# 6-CODEC.net
KiCad netlist of a schematic drawn in Altium Designer
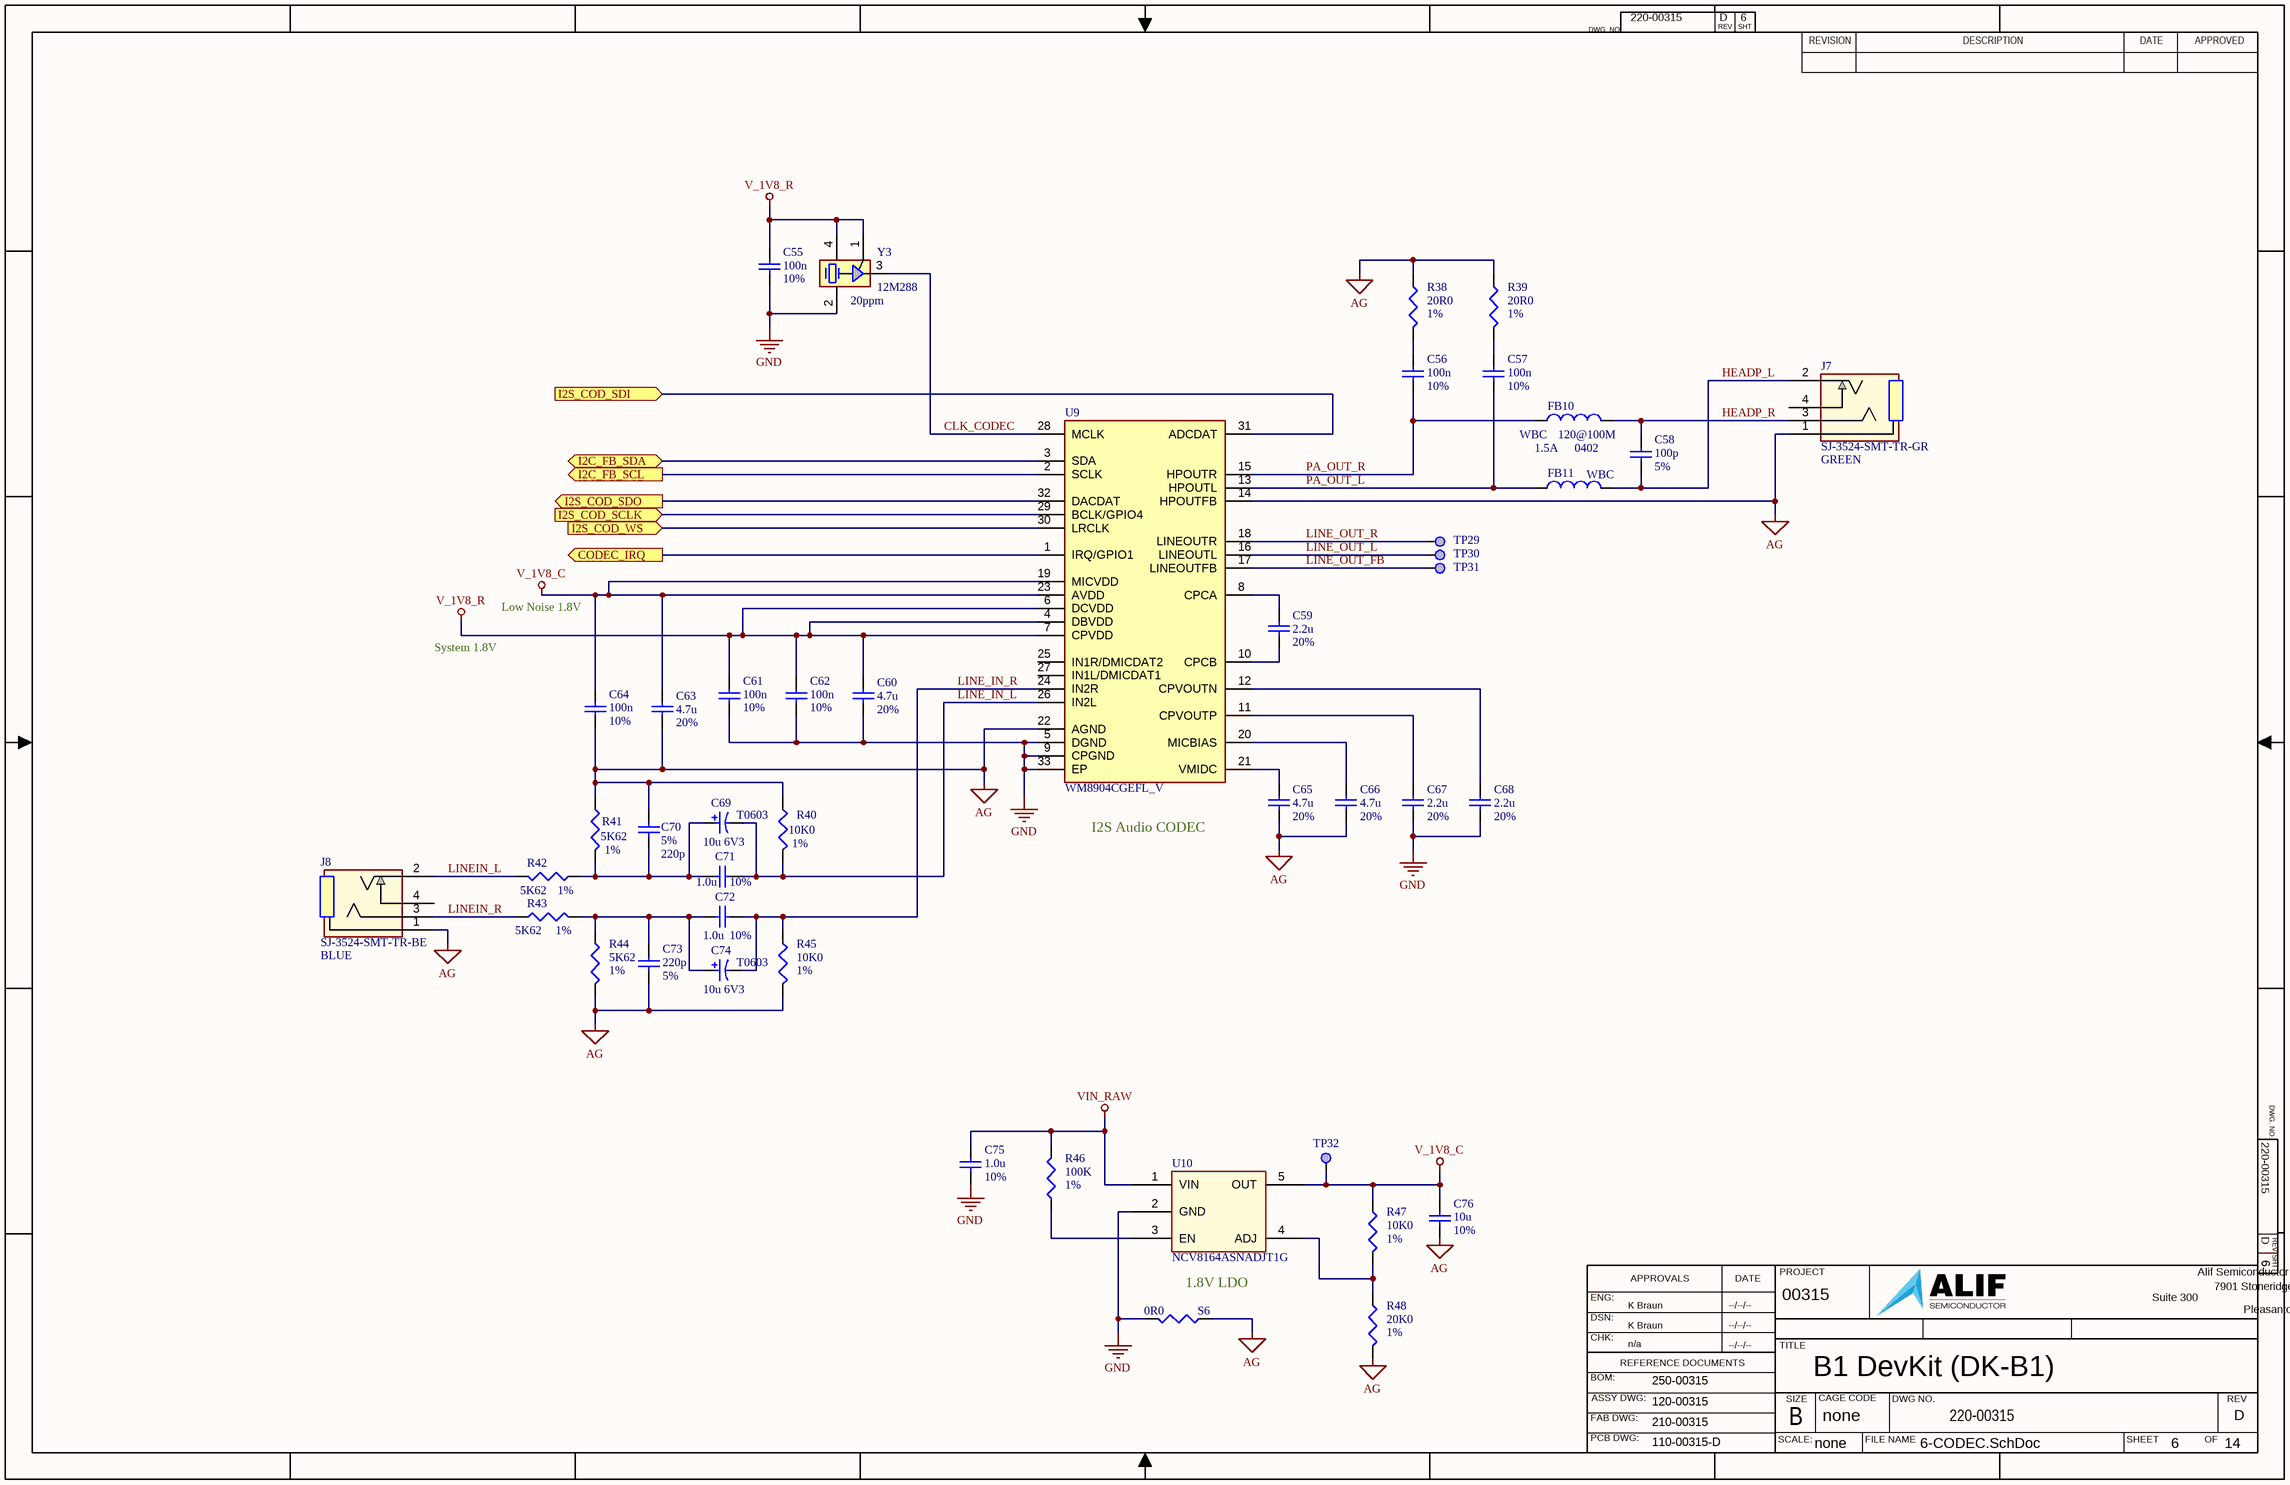
[diagram p0: 6-CODEC.SchDoc]

(export (version "E")
  (design (tool "Eeschema 10.0.6"))
  (components
    (comp (ref "C55")
      (value "100n")
      (footprint "CAPC0402-01")
      (description "Cap,100nF,10%,50V,X7R,0402")
      (fields
        (field (name "VOLTAGE") "50V")
        (field (name "TOLERANCE") "10%")
        (field (name "Comment") "Cap")
        (field (name "PUBLISHER") "Altium Limited")
      )
      (libsource (lib "kb1") (part "Cap"))
    )
    (comp (ref "C56")
      (value "100n")
      (footprint "CAPC0402-01")
      (description "Cap,100nF,10%,50V,X7R,0402")
      (fields
        (field (name "VOLTAGE") "50V")
        (field (name "TOLERANCE") "10%")
        (field (name "Comment") "Cap")
        (field (name "PUBLISHER") "Altium Limited")
      )
      (libsource (lib "kb1") (part "Cap"))
    )
    (comp (ref "C57")
      (value "100n")
      (footprint "CAPC0402-01")
      (description "Cap,100nF,10%,50V,X7R,0402")
      (fields
        (field (name "VOLTAGE") "50V")
        (field (name "TOLERANCE") "10%")
        (field (name "Comment") "Cap")
        (field (name "PUBLISHER") "Altium Limited")
      )
      (libsource (lib "kb1") (part "Cap"))
    )
    (comp (ref "C58")
      (value "100p")
      (footprint "CAPC0402-01")
      (description "Cap,100pF,5%,25V,C0G,Hi-Q,0402")
      (fields
        (field (name "VOLTAGE") "25V")
        (field (name "TOLERANCE") "5%")
        (field (name "Comment") "Cap")
        (field (name "PUBLISHER") "Altium Limited")
      )
      (libsource (lib "kb1") (part "Cap"))
    )
    (comp (ref "C59")
      (value "2.2u")
      (footprint "CAPC0402-01")
      (description "Cap,2.2uF,20%,25V,X5R,0402")
      (fields
        (field (name "VOLTAGE") "25V")
        (field (name "TOLERANCE") "20%")
        (field (name "Comment") "Cap_225M25VX5R0402_1")
        (field (name "PUBLISHER") "Altium Limited")
      )
      (libsource (lib "Alif-2") (part "Cap_225M25VX5R0402_1"))
    )
    (comp (ref "C60")
      (value "4.7u")
      (footprint "CAPC0402-01")
      (description "Cap,4.7uF,20%,10V,X5R,0402")
      (fields
        (field (name "VOLTAGE") "10V")
        (field (name "TOLERANCE") "20%")
        (field (name "Comment") "Cap")
        (field (name "PUBLISHER") "Altium Limited")
      )
      (libsource (lib "Alif-2") (part "Cap_225M25VX5R0402_1"))
    )
    (comp (ref "C61")
      (value "100n")
      (footprint "CAPC0402-01")
      (description "Cap,100nF,10%,50V,X7R,0402")
      (fields
        (field (name "VOLTAGE") "50V")
        (field (name "TOLERANCE") "10%")
        (field (name "Comment") "Cap")
        (field (name "PUBLISHER") "Altium Limited")
      )
      (libsource (lib "kb1") (part "Cap"))
    )
    (comp (ref "C62")
      (value "100n")
      (footprint "CAPC0402-01")
      (description "Cap,100nF,10%,50V,X7R,0402")
      (fields
        (field (name "VOLTAGE") "50V")
        (field (name "TOLERANCE") "10%")
        (field (name "Comment") "Cap")
        (field (name "PUBLISHER") "Altium Limited")
      )
      (libsource (lib "kb1") (part "Cap"))
    )
    (comp (ref "C63")
      (value "4.7u")
      (footprint "CAPC0402-01")
      (description "Cap,4.7uF,20%,10V,X5R,0402")
      (fields
        (field (name "VOLTAGE") "10V")
        (field (name "TOLERANCE") "20%")
        (field (name "Comment") "Cap")
        (field (name "PUBLISHER") "Altium Limited")
      )
      (libsource (lib "Alif-2") (part "Cap_225M25VX5R0402_1"))
    )
    (comp (ref "C64")
      (value "100n")
      (footprint "CAPC0402-01")
      (description "Cap,100nF,10%,50V,X7R,0402")
      (fields
        (field (name "VOLTAGE") "50V")
        (field (name "TOLERANCE") "10%")
        (field (name "Comment") "Cap")
        (field (name "PUBLISHER") "Altium Limited")
      )
      (libsource (lib "kb1") (part "Cap"))
    )
    (comp (ref "C65")
      (value "4.7u")
      (footprint "CAPC0402-01")
      (description "Cap,4.7uF,20%,10V,X5R,0402")
      (fields
        (field (name "VOLTAGE") "10V")
        (field (name "TOLERANCE") "20%")
        (field (name "Comment") "Cap")
        (field (name "PUBLISHER") "Altium Limited")
      )
      (libsource (lib "Alif-2") (part "Cap_225M25VX5R0402_1"))
    )
    (comp (ref "C66")
      (value "4.7u")
      (footprint "CAPC0402-01")
      (description "Cap,4.7uF,20%,10V,X5R,0402")
      (fields
        (field (name "VOLTAGE") "10V")
        (field (name "TOLERANCE") "20%")
        (field (name "Comment") "Cap")
        (field (name "PUBLISHER") "Altium Limited")
      )
      (libsource (lib "Alif-2") (part "Cap_225M25VX5R0402_1"))
    )
    (comp (ref "C67")
      (value "2.2u")
      (footprint "CAPC0402-01")
      (description "Cap,2.2uF,20%,25V,X5R,0402")
      (fields
        (field (name "VOLTAGE") "25V")
        (field (name "TOLERANCE") "20%")
        (field (name "Comment") "Cap_225M25VX5R0402_1")
        (field (name "PUBLISHER") "Altium Limited")
      )
      (libsource (lib "Alif-2") (part "Cap_225M25VX5R0402_1"))
    )
    (comp (ref "C68")
      (value "2.2u")
      (footprint "CAPC0402-01")
      (description "Cap,2.2uF,20%,25V,X5R,0402")
      (fields
        (field (name "VOLTAGE") "25V")
        (field (name "TOLERANCE") "20%")
        (field (name "Comment") "Cap_225M25VX5R0402_1")
        (field (name "PUBLISHER") "Altium Limited")
      )
      (libsource (lib "Alif-2") (part "Cap_225M25VX5R0402_1"))
    )
    (comp (ref "C69")
      (value "10u 6V3")
      (footprint "CAP_0603_TCS_M_ROM-L")
      (description "Cap, Tant, 10uF, 6V3-10V, 10%-20%, 0603")
      (fields (field (name "CASE SIZE/DIMENSION") "T0603") (field (name "Comment") "CAP-P"))
      (libsource (lib "Alif-2") (part "CAP-P"))
    )
    (comp (ref "C70")
      (value "220p")
      (footprint "CAPC0402-01")
      (description "Cap,220pF,5%,50V,C0G,0402")
      (fields
        (field (name "VOLTAGE") "50V")
        (field (name "TOLERANCE") "5%")
        (field (name "Comment") "Cap")
        (field (name "PUBLISHER") "Altium Limited")
      )
      (libsource (lib "kb1") (part "Cap"))
    )
    (comp (ref "C71")
      (value "1.0u")
      (footprint "CAPC0402-01")
      (description "Cap,1.0uF,20%,25V,X5R,0402")
      (fields
        (field (name "VOLTAGE") "25V")
        (field (name "TOLERANCE") "10%")
        (field (name "Comment") "Cap")
        (field (name "PUBLISHER") "Altium Limited")
      )
      (libsource (lib "kb1") (part "Cap"))
    )
    (comp (ref "C72")
      (value "1.0u")
      (footprint "CAPC0402-01")
      (description "Cap,1.0uF,20%,25V,X5R,0402")
      (fields
        (field (name "VOLTAGE") "25V")
        (field (name "TOLERANCE") "10%")
        (field (name "Comment") "Cap")
        (field (name "PUBLISHER") "Altium Limited")
      )
      (libsource (lib "kb1") (part "Cap"))
    )
    (comp (ref "C73")
      (value "220p")
      (footprint "CAPC0402-01")
      (description "Cap,220pF,5%,50V,C0G,0402")
      (fields
        (field (name "VOLTAGE") "50V")
        (field (name "TOLERANCE") "5%")
        (field (name "Comment") "Cap")
        (field (name "PUBLISHER") "Altium Limited")
      )
      (libsource (lib "kb1") (part "Cap"))
    )
    (comp (ref "C74")
      (value "10u 6V3")
      (footprint "CAP_0603_TCS_M_ROM-L")
      (description "Cap, Tant, 10uF, 6V3-10V, 10%-20%, 0603")
      (fields (field (name "CASE SIZE/DIMENSION") "T0603") (field (name "Comment") "CAP-P"))
      (libsource (lib "Alif-2") (part "CAP-P"))
    )
    (comp (ref "C75")
      (value "1.0u")
      (footprint "CAPC0402-01")
      (description "Cap,1.0uF,20%,25V,X5R,0402")
      (fields
        (field (name "VOLTAGE") "25V")
        (field (name "TOLERANCE") "10%")
        (field (name "Comment") "Cap")
        (field (name "PUBLISHER") "Altium Limited")
      )
      (libsource (lib "kb1") (part "Cap"))
    )
    (comp (ref "C76")
      (value "10u")
      (footprint "CAPC0402-01")
      (description "Cap,10uF,20%,10V,X5R,0402")
      (fields
        (field (name "VOLTAGE") "10V")
        (field (name "TOLERANCE") "10%")
        (field (name "Comment") "Cap")
        (field (name "PUBLISHER") "Altium Limited")
      )
      (libsource (lib "kb1") (part "Cap"))
    )
    (comp (ref "FB10")
      (value "WBC")
      (footprint "FB_0402_MuRata_as_R0402")
      (description "Ind,WidebandChoke,1.5A,120ohm@100MHz,95mOhm,0402")
      (fields
        (field (name "TOLERANCE") "30%")
        (field (name "IMPEDANCE") "120@100M")
        (field (name "PCB_FOOTPRINT") "0402")
        (field (name "RMS_CURRENT") "1.5A")
        (field (name "Comment") "Ind_WBC_1A5_120@100M0402_1")
        (field (name "PUBLISHER") "Altium Limited")
      )
      (libsource (lib "Alif2") (part "Ind_WBC_1A5_120@100M0402_1"))
    )
    (comp (ref "FB11")
      (value "WBC")
      (footprint "FB_0402_MuRata_as_R0402")
      (description "Ind,WidebandChoke,1.5A,120ohm@100MHz,95mOhm,0402")
      (fields
        (field (name "TOLERANCE") "30%")
        (field (name "Comment") "Ind_WBC_1A5_120@100M0402_1")
        (field (name "PUBLISHER") "Altium Limited")
      )
      (libsource (lib "Alif2") (part "Ind_WBC_1A5_120@100M0402_1"))
    )
    (comp (ref "J7")
      (value "SJ-3524-SMT-TR-GR")
      (footprint "CONN_CUI_SJ-3524-SMT-TR-XX_CUD")
      (fields (field (name "COLOR") "GREEN"))
      (libsource (lib "") (part "CONN_SJ-3524-SMT-TR-XX_1"))
    )
    (comp (ref "J8")
      (value "SJ-3524-SMT-TR-BE")
      (footprint "CONN_CUI_SJ-3524-SMT-TR-XX_CUD")
      (description "Conn, Audio Jack, 3.5 mm Low Profile Surface Mount Stereo Jack, 3 Pin Right-Angle, XX = color BLUE")
      (fields (field (name "COLOR") "BLUE"))
      (libsource (lib "Alif-2") (part "CONN_SJ-3524-SMT-TR-XX"))
    )
    (comp (ref "R38")
      (value "20R0")
      (footprint "RESC0402-01")
      (description "Res,20R0,1%,100ppm,0402")
      (fields
        (field (name "TOLERANCE") "1%")
        (field (name "Comment") "Res3")
        (field (name "PUBLISHER") "Altium Limited")
      )
      (libsource (lib "kb1") (part "Res3"))
    )
    (comp (ref "R39")
      (value "20R0")
      (footprint "RESC0402-01")
      (description "Res,20R0,1%,100ppm,0402")
      (fields
        (field (name "TOLERANCE") "1%")
        (field (name "Comment") "Res3")
        (field (name "PUBLISHER") "Altium Limited")
      )
      (libsource (lib "kb1") (part "Res3"))
    )
    (comp (ref "R40")
      (value "10K0")
      (footprint "RESC0402-01")
      (description "Res,10K0,1%,100ppm,0402")
      (fields
        (field (name "TOLERANCE") "1%")
        (field (name "Comment") "Res3")
        (field (name "PUBLISHER") "Altium Limited")
      )
      (libsource (lib "kb1") (part "Res3"))
    )
    (comp (ref "R41")
      (value "5K62")
      (footprint "RESC0402-01")
      (description "Res,5K62,1%,100ppm,0402")
      (fields
        (field (name "TOLERANCE") "1%")
        (field (name "Comment") "Res3")
        (field (name "PUBLISHER") "Altium Limited")
      )
      (libsource (lib "kb1") (part "Res3"))
    )
    (comp (ref "R42")
      (value "5K62")
      (footprint "RESC0402-01")
      (description "Res,5K62,1%,100ppm,0402")
      (fields
        (field (name "TOLERANCE") "1%")
        (field (name "Comment") "Res3")
        (field (name "PUBLISHER") "Altium Limited")
      )
      (libsource (lib "kb1") (part "Res3"))
    )
    (comp (ref "R43")
      (value "5K62")
      (footprint "RESC0402-01")
      (description "Res,5K62,1%,100ppm,0402")
      (fields
        (field (name "TOLERANCE") "1%")
        (field (name "Comment") "Res3")
        (field (name "PUBLISHER") "Altium Limited")
      )
      (libsource (lib "kb1") (part "Res3"))
    )
    (comp (ref "R44")
      (value "5K62")
      (footprint "RESC0402-01")
      (description "Res,5K62,1%,100ppm,0402")
      (fields
        (field (name "TOLERANCE") "1%")
        (field (name "Comment") "Res3")
        (field (name "PUBLISHER") "Altium Limited")
      )
      (libsource (lib "kb1") (part "Res3"))
    )
    (comp (ref "R45")
      (value "10K0")
      (footprint "RESC0402-01")
      (description "Res,10K0,1%,100ppm,0402")
      (fields
        (field (name "TOLERANCE") "1%")
        (field (name "Comment") "Res3")
        (field (name "PUBLISHER") "Altium Limited")
      )
      (libsource (lib "kb1") (part "Res3"))
    )
    (comp (ref "R46")
      (value "100K")
      (footprint "RESC0402-01")
      (description "Res,100K,1%,100ppm,0402")
      (fields
        (field (name "TOLERANCE") "1%")
        (field (name "Comment") "Res3")
        (field (name "PUBLISHER") "Altium Limited")
      )
      (libsource (lib "kb1") (part "Res3"))
    )
    (comp (ref "R47")
      (value "10K0")
      (footprint "RESC0402-01")
      (description "Res,10K0,1%,100ppm,0402")
      (fields
        (field (name "TOLERANCE") "1%")
        (field (name "Comment") "Res3")
        (field (name "PUBLISHER") "Altium Limited")
      )
      (libsource (lib "kb1") (part "Res3"))
    )
    (comp (ref "R48")
      (value "20K0")
      (footprint "RESC0402-01")
      (description "Res,20K0,1%,100ppm,0402")
      (fields
        (field (name "TOLERANCE") "1%")
        (field (name "Comment") "Res3")
        (field (name "PUBLISHER") "Altium Limited")
      )
      (libsource (lib "kb1") (part "Res3"))
    )
    (comp (ref "S6")
      (value "0R0")
      (footprint "RESC0402-01")
      (description "Res,0R ohm,Jumper,0402")
      (fields
        (field (name "TOLERANCE") "JMPR")
        (field (name "Comment") "Res3")
        (field (name "PUBLISHER") "Altium Limited")
      )
      (libsource (lib "kb1") (part "Res3"))
    )
    (comp (ref "TP29")
      (value "TP_SMPAD")
      (footprint "TP_30_RND")
      (description "Test Point, SMT Pad,--not a BOM item--")
      (libsource (lib "Alif-2") (part "TP_SMPAD"))
    )
    (comp (ref "TP30")
      (value "TP_SMPAD")
      (footprint "TP_30_RND")
      (description "Test Point, SMT Pad,--not a BOM item--")
      (libsource (lib "Alif-2") (part "TP_SMPAD"))
    )
    (comp (ref "TP31")
      (value "TP_SMPAD")
      (footprint "TP_30_RND")
      (description "Test Point, SMT Pad,--not a BOM item--")
      (libsource (lib "Alif-2") (part "TP_SMPAD"))
    )
    (comp (ref "TP32")
      (value "TP_SMPAD")
      (footprint "TP_30_RND")
      (description "Test Point, SMT Pad,--not a BOM item--")
      (libsource (lib "Alif-2") (part "TP_SMPAD"))
    )
    (comp (ref "U9")
      (value "WM8904CGEFL_V")
      (footprint "QFN40P400X400X80-33N")
      (description "IC, Audio CODEC, Ultra Low Pwr, 1.8V, QFN32")
      (fields (field (name "MOUSER PART NUMBER") "238-WM8904CGEFL/V"))
      (libsource (lib "Alif-2") (part "IC_CODEC_WM8904CGEFL_V"))
    )
    (comp (ref "U10")
      (value "NCV8164ASNADJT1G")
      (footprint "TSOT23-5_ONS")
      (description "IC, LDO,Adj 1.2V - 5.5V,300mA,SOT23-5")
      (libsource (lib "Alif-2") (part "IC_LDO_NCV8164ASNADJT1G"))
    )
    (comp (ref "Y3")
      (value "12M288")
      (footprint "OSC_4P_3225_1210_uChip_DSC1001DL5")
      (description "Oscillator, XO, 12.288MHz, 20ppm, 1.8V, 2520(1008)-4P")
      (fields
        (field (name "TOLERANCE") "20ppm")
        (field (name "Comment") "XO_12M288")
        (field (name "PUBLISHER") "Altium Limited")
      )
      (libsource (lib "Alif-2") (part "Osc_12M288_20ppm_1V8_3225"))
    )
  )
  (nets
    (net (code "1") (name "/CLK_CODEC") (class "Default")
      (node (ref "U9") (pin "28") (pinfunction "MCLK_28") (pintype "passive"))
      (node (ref "Y3") (pin "3") (pinfunction "OUT_3") (pintype "passive"))
    )
    (net (code "2") (name "/CODEC_IRQ") (class "Default")
      (node (ref "U9") (pin "1") (pinfunction "IRQ/GPIO1_1") (pintype "passive"))
    )
    (net (code "3") (name "/HEADP_L") (class "Default")
      (node (ref "C58") (pin "1") (pinfunction "1_1") (pintype "passive"))
      (node (ref "FB11") (pin "2") (pinfunction "2_2") (pintype "passive"))
      (node (ref "J7") (pin "2") (pinfunction "2_2") (pintype "passive"))
    )
    (net (code "4") (name "/HEADP_R") (class "Default")
      (node (ref "C58") (pin "2") (pinfunction "2_2") (pintype "passive"))
      (node (ref "FB10") (pin "2") (pinfunction "2_2") (pintype "passive"))
      (node (ref "J7") (pin "3") (pinfunction "3_3") (pintype "passive"))
    )
    (net (code "5") (name "/I2C_FB_SCL") (class "Default")
      (node (ref "U9") (pin "2") (pinfunction "SCLK_2") (pintype "passive"))
    )
    (net (code "6") (name "/I2C_FB_SDA") (class "Default")
      (node (ref "U9") (pin "3") (pinfunction "SDA_3") (pintype "passive"))
    )
    (net (code "7") (name "/I2S_COD_SCLK") (class "Default")
      (node (ref "U9") (pin "29") (pinfunction "BCLK/GPIO4_29") (pintype "passive"))
    )
    (net (code "8") (name "/I2S_COD_SDI") (class "Default")
      (node (ref "U9") (pin "31") (pinfunction "ADCDAT_31") (pintype "passive"))
    )
    (net (code "9") (name "/I2S_COD_SDO") (class "Default")
      (node (ref "U9") (pin "32") (pinfunction "DACDAT_32") (pintype "passive"))
    )
    (net (code "10") (name "/I2S_COD_WS") (class "Default")
      (node (ref "U9") (pin "30") (pinfunction "LRCLK_30") (pintype "passive"))
    )
    (net (code "11") (name "/LINEIN_L") (class "Default")
      (node (ref "J8") (pin "2") (pinfunction "2_2") (pintype "passive"))
      (node (ref "R42") (pin "1") (pinfunction "1_1") (pintype "passive"))
    )
    (net (code "12") (name "/LINEIN_R") (class "Default")
      (node (ref "J8") (pin "3") (pinfunction "3_3") (pintype "passive"))
      (node (ref "R43") (pin "1") (pinfunction "1_1") (pintype "passive"))
    )
    (net (code "13") (name "/LINE_IN_L") (class "Default")
      (node (ref "C69") (pin "2") (pinfunction "2_2") (pintype "passive"))
      (node (ref "C71") (pin "1") (pinfunction "1_1") (pintype "passive"))
      (node (ref "R40") (pin "1") (pinfunction "1_1") (pintype "passive"))
      (node (ref "U9") (pin "26") (pinfunction "IN2L_26") (pintype "passive"))
    )
    (net (code "14") (name "/LINE_IN_R") (class "Default")
      (node (ref "C72") (pin "1") (pinfunction "1_1") (pintype "passive"))
      (node (ref "C74") (pin "2") (pinfunction "2_2") (pintype "passive"))
      (node (ref "R45") (pin "1") (pinfunction "1_1") (pintype "passive"))
      (node (ref "U9") (pin "24") (pinfunction "IN2R_24") (pintype "passive"))
    )
    (net (code "15") (name "/LINE_OUT_FB") (class "Default")
      (node (ref "TP31") (pin "1") (pinfunction "1_1") (pintype "passive"))
      (node (ref "U9") (pin "17") (pinfunction "LINEOUTFB_17") (pintype "passive"))
    )
    (net (code "16") (name "/LINE_OUT_L") (class "Default")
      (node (ref "TP30") (pin "1") (pinfunction "1_1") (pintype "passive"))
      (node (ref "U9") (pin "16") (pinfunction "LINEOUTL_16") (pintype "passive"))
    )
    (net (code "17") (name "/LINE_OUT_R") (class "Default")
      (node (ref "TP29") (pin "1") (pinfunction "1_1") (pintype "passive"))
      (node (ref "U9") (pin "18") (pinfunction "LINEOUTR_18") (pintype "passive"))
    )
    (net (code "18") (name "/PA_OUT_L") (class "Default")
      (node (ref "C57") (pin "1") (pinfunction "1_1") (pintype "passive"))
      (node (ref "FB11") (pin "1") (pinfunction "1_1") (pintype "passive"))
      (node (ref "U9") (pin "13") (pinfunction "HPOUTL_13") (pintype "passive"))
    )
    (net (code "19") (name "/PA_OUT_R") (class "Default")
      (node (ref "C56") (pin "1") (pinfunction "1_1") (pintype "passive"))
      (node (ref "FB10") (pin "1") (pinfunction "1_1") (pintype "passive"))
      (node (ref "U9") (pin "15") (pinfunction "HPOUTR_15") (pintype "passive"))
    )
    (net (code "20") (name "AG") (class "Default")
      (node (ref "C63") (pin "1") (pinfunction "1_1") (pintype "passive"))
      (node (ref "C64") (pin "1") (pinfunction "1_1") (pintype "passive"))
      (node (ref "C65") (pin "1") (pinfunction "1_1") (pintype "passive"))
      (node (ref "C66") (pin "1") (pinfunction "1_1") (pintype "passive"))
      (node (ref "C70") (pin "1") (pinfunction "1_1") (pintype "passive"))
      (node (ref "C73") (pin "1") (pinfunction "1_1") (pintype "passive"))
      (node (ref "C76") (pin "1") (pinfunction "1_1") (pintype "passive"))
      (node (ref "J7") (pin "1") (pinfunction "1_1") (pintype "passive"))
      (node (ref "J8") (pin "1") (pinfunction "1_1") (pintype "passive"))
      (node (ref "R38") (pin "1") (pinfunction "1_1") (pintype "passive"))
      (node (ref "R39") (pin "1") (pinfunction "1_1") (pintype "passive"))
      (node (ref "R40") (pin "2") (pinfunction "2_2") (pintype "passive"))
      (node (ref "R41") (pin "2") (pinfunction "2_2") (pintype "passive"))
      (node (ref "R44") (pin "2") (pinfunction "2_2") (pintype "passive"))
      (node (ref "R45") (pin "2") (pinfunction "2_2") (pintype "passive"))
      (node (ref "R48") (pin "2") (pinfunction "2_2") (pintype "passive"))
      (node (ref "S6") (pin "1") (pinfunction "1_1") (pintype "passive"))
      (node (ref "U9") (pin "14") (pinfunction "HPOUTFB_14") (pintype "passive"))
      (node (ref "U9") (pin "22") (pinfunction "AGND_22") (pintype "passive"))
    )
    (net (code "21") (name "GND") (class "Default")
      (node (ref "C55") (pin "1") (pinfunction "1_1") (pintype "passive"))
      (node (ref "C60") (pin "1") (pinfunction "1_1") (pintype "passive"))
      (node (ref "C61") (pin "1") (pinfunction "1_1") (pintype "passive"))
      (node (ref "C62") (pin "1") (pinfunction "1_1") (pintype "passive"))
      (node (ref "C67") (pin "1") (pinfunction "1_1") (pintype "passive"))
      (node (ref "C68") (pin "1") (pinfunction "1_1") (pintype "passive"))
      (node (ref "C75") (pin "1") (pinfunction "1_1") (pintype "passive"))
      (node (ref "S6") (pin "2") (pinfunction "2_2") (pintype "passive"))
      (node (ref "U10") (pin "2") (pinfunction "GND_2") (pintype "passive"))
      (node (ref "U9") (pin "33") (pinfunction "EP_33") (pintype "passive"))
      (node (ref "U9") (pin "5") (pinfunction "DGND_5") (pintype "passive"))
      (node (ref "U9") (pin "9") (pinfunction "CPGND_9") (pintype "passive"))
      (node (ref "Y3") (pin "2") (pinfunction "G2_2") (pintype "passive"))
    )
    (net (code "22") (name "Net-(C56-Pad2)") (class "Default")
      (node (ref "C56") (pin "2") (pinfunction "2_2") (pintype "passive"))
      (node (ref "R38") (pin "2") (pinfunction "2_2") (pintype "passive"))
    )
    (net (code "23") (name "Net-(C57-Pad2)") (class "Default")
      (node (ref "C57") (pin "2") (pinfunction "2_2") (pintype "passive"))
      (node (ref "R39") (pin "2") (pinfunction "2_2") (pintype "passive"))
    )
    (net (code "24") (name "Net-(C69-Pad1)") (class "Default")
      (node (ref "C69") (pin "1") (pinfunction "1_1") (pintype "passive"))
      (node (ref "C70") (pin "2") (pinfunction "2_2") (pintype "passive"))
      (node (ref "C71") (pin "2") (pinfunction "2_2") (pintype "passive"))
      (node (ref "R41") (pin "1") (pinfunction "1_1") (pintype "passive"))
      (node (ref "R42") (pin "2") (pinfunction "2_2") (pintype "passive"))
    )
    (net (code "25") (name "Net-(C72-Pad2)") (class "Default")
      (node (ref "C72") (pin "2") (pinfunction "2_2") (pintype "passive"))
      (node (ref "C73") (pin "2") (pinfunction "2_2") (pintype "passive"))
      (node (ref "C74") (pin "1") (pinfunction "1_1") (pintype "passive"))
      (node (ref "R43") (pin "2") (pinfunction "2_2") (pintype "passive"))
      (node (ref "R44") (pin "1") (pinfunction "1_1") (pintype "passive"))
    )
    (net (code "26") (name "Net-(U9-CPCA)") (class "Default")
      (node (ref "C59") (pin "2") (pinfunction "2_2") (pintype "passive"))
      (node (ref "U9") (pin "8") (pinfunction "CPCA_8") (pintype "passive"))
    )
    (net (code "27") (name "Net-(U9-CPCB)") (class "Default")
      (node (ref "C59") (pin "1") (pinfunction "1_1") (pintype "passive"))
      (node (ref "U9") (pin "10") (pinfunction "CPCB_10") (pintype "passive"))
    )
    (net (code "28") (name "Net-(U9-CPVOUTN)") (class "Default")
      (node (ref "C68") (pin "2") (pinfunction "2_2") (pintype "passive"))
      (node (ref "U9") (pin "12") (pinfunction "CPVOUTN_12") (pintype "passive"))
    )
    (net (code "29") (name "Net-(U9-CPVOUTP)") (class "Default")
      (node (ref "C67") (pin "2") (pinfunction "2_2") (pintype "passive"))
      (node (ref "U9") (pin "11") (pinfunction "CPVOUTP_11") (pintype "passive"))
    )
    (net (code "30") (name "Net-(U9-MICBIAS)") (class "Default")
      (node (ref "C66") (pin "2") (pinfunction "2_2") (pintype "passive"))
      (node (ref "U9") (pin "20") (pinfunction "MICBIAS_20") (pintype "passive"))
    )
    (net (code "31") (name "Net-(U9-VMIDC)") (class "Default")
      (node (ref "C65") (pin "2") (pinfunction "2_2") (pintype "passive"))
      (node (ref "U9") (pin "21") (pinfunction "VMIDC_21") (pintype "passive"))
    )
    (net (code "32") (name "Net-(U10-ADJ)") (class "Default")
      (node (ref "R47") (pin "2") (pinfunction "2_2") (pintype "passive"))
      (node (ref "R48") (pin "1") (pinfunction "1_1") (pintype "passive"))
      (node (ref "U10") (pin "4") (pinfunction "ADJ_4") (pintype "passive"))
    )
    (net (code "33") (name "Net-(U10-EN)") (class "Default")
      (node (ref "R46") (pin "1") (pinfunction "1_1") (pintype "passive"))
      (node (ref "U10") (pin "3") (pinfunction "EN_3") (pintype "passive"))
    )
    (net (code "34") (name "VIN_RAW") (class "Default")
      (node (ref "C75") (pin "2") (pinfunction "2_2") (pintype "passive"))
      (node (ref "R46") (pin "2") (pinfunction "2_2") (pintype "passive"))
      (node (ref "U10") (pin "1") (pinfunction "VIN_1") (pintype "passive"))
    )
    (net (code "35") (name "V_1V8_C") (class "Default")
      (node (ref "C63") (pin "2") (pinfunction "2_2") (pintype "passive"))
      (node (ref "C64") (pin "2") (pinfunction "2_2") (pintype "passive"))
      (node (ref "C76") (pin "2") (pinfunction "2_2") (pintype "passive"))
      (node (ref "R47") (pin "1") (pinfunction "1_1") (pintype "passive"))
      (node (ref "TP32") (pin "1") (pinfunction "1_1") (pintype "passive"))
      (node (ref "U10") (pin "5") (pinfunction "OUT_5") (pintype "passive"))
      (node (ref "U9") (pin "19") (pinfunction "MICVDD_19") (pintype "passive"))
      (node (ref "U9") (pin "23") (pinfunction "AVDD_23") (pintype "passive"))
    )
    (net (code "36") (name "V_1V8_R") (class "Default")
      (node (ref "C55") (pin "2") (pinfunction "2_2") (pintype "passive"))
      (node (ref "C60") (pin "2") (pinfunction "2_2") (pintype "passive"))
      (node (ref "C61") (pin "2") (pinfunction "2_2") (pintype "passive"))
      (node (ref "C62") (pin "2") (pinfunction "2_2") (pintype "passive"))
      (node (ref "U9") (pin "4") (pinfunction "DBVDD_4") (pintype "passive"))
      (node (ref "U9") (pin "6") (pinfunction "DCVDD_6") (pintype "passive"))
      (node (ref "U9") (pin "7") (pinfunction "CPVDD_7") (pintype "passive"))
      (node (ref "Y3") (pin "1") (pinfunction "G1_1") (pintype "passive"))
      (node (ref "Y3") (pin "4") (pinfunction "VDD_4") (pintype "passive"))
    )
    (net (code "37") (name "unconnected-(J7-Pad4)") (class "Default")
      (node (ref "J7") (pin "4") (pinfunction "4_4") (pintype "passive"))
    )
    (net (code "38") (name "unconnected-(J8-Pad4)") (class "Default")
      (node (ref "J8") (pin "4") (pinfunction "4_4") (pintype "passive"))
    )
    (net (code "39") (name "unconnected-(U9-IN1L{slash}DMICDAT1-Pad27)") (class "Default")
      (node (ref "U9") (pin "27") (pinfunction "IN1L/DMICDAT1_27") (pintype "passive"))
    )
    (net (code "40") (name "unconnected-(U9-IN1R{slash}DMICDAT2-Pad25)") (class "Default")
      (node (ref "U9") (pin "25") (pinfunction "IN1R/DMICDAT2_25") (pintype "passive"))
    )
  )
)
